# HW.net
KiCad netlist of a schematic drawn in Altium Designer
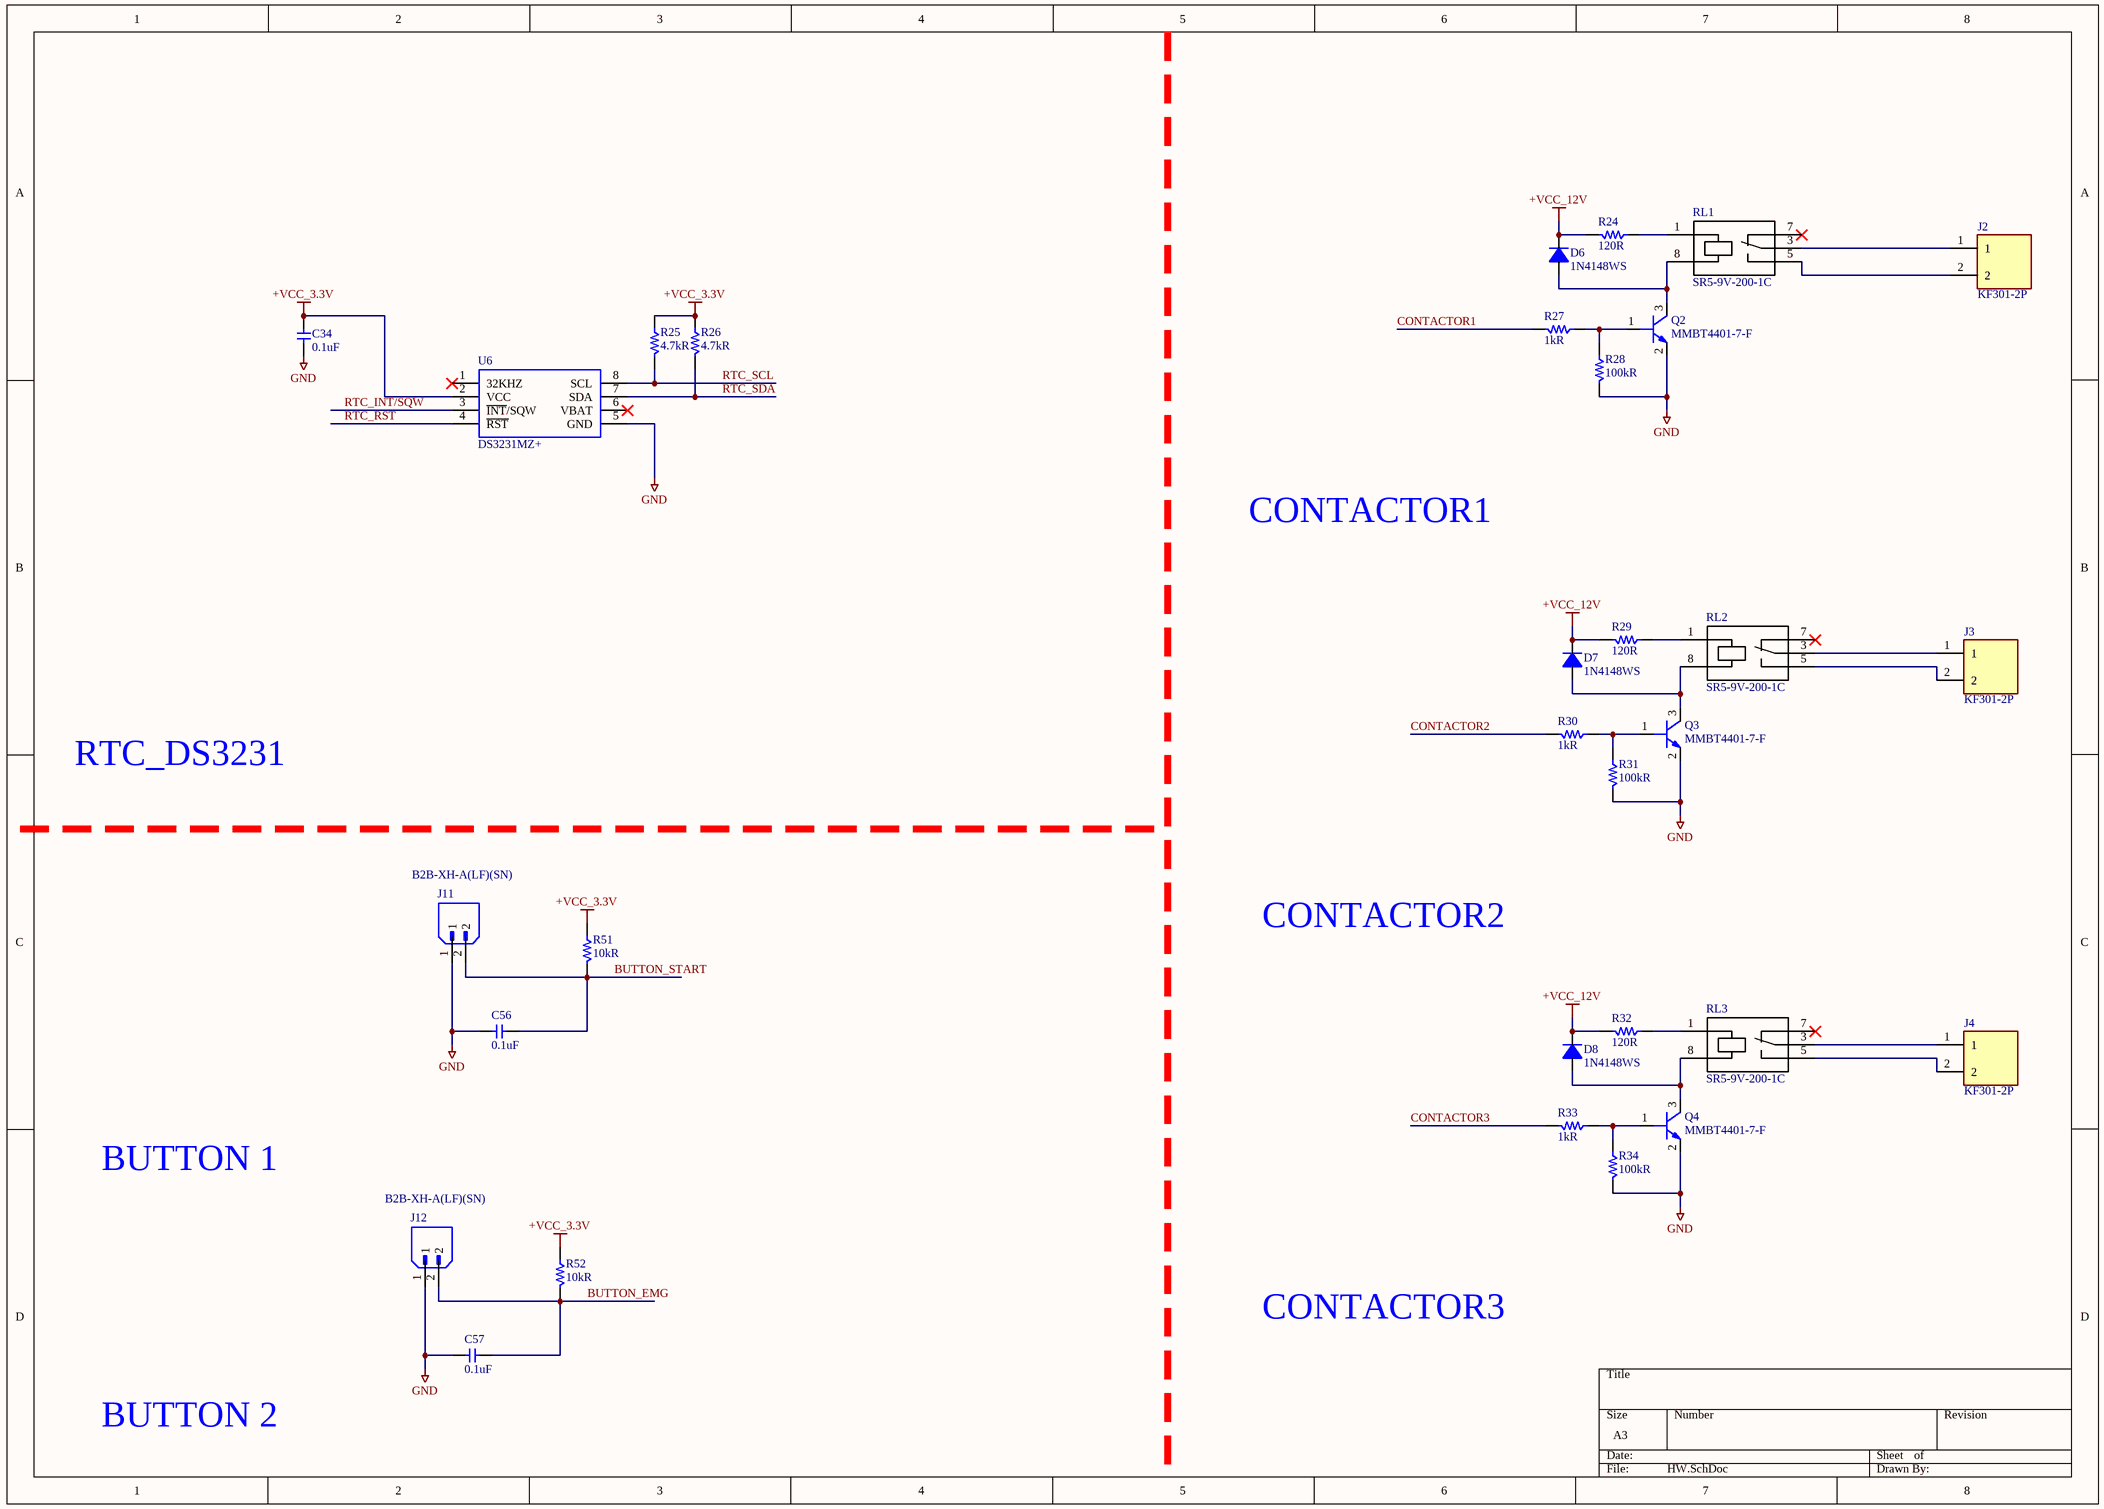
[diagram p0: HW.SchDoc]

(export (version "E")
  (design (tool "Eeschema 10.0.6"))
  (components
    (comp (ref "C34")
      (value "0.1uF")
      (footprint "CAP 0402 (1005)")
      (description "50V 100nF ±10% 0402 Multilayer Ceramic Capacitors MLCC - SMD/SMT ROHS")
      (fields
        (field (name "MANUFACTURER") "Samwha Capacitor")
        (field (name "MANUFACTURER PART NUMBER") "CS1005X7R104K500NR")
      )
      (libsource (lib "BSR NODE_V2.0 LIB") (part "CAP0402 0.1uF 50V"))
    )
    (comp (ref "C56")
      (value "0.1uF")
      (footprint "CAP 0402 (1005)")
      (description "50V 100nF ±10% 0402 Multilayer Ceramic Capacitors MLCC - SMD/SMT ROHS")
      (fields
        (field (name "MANUFACTURER") "Samwha Capacitor")
        (field (name "MANUFACTURER PART NUMBER") "CS1005X7R104K500NR")
      )
      (libsource (lib "BSR NODE_V2.0 LIB") (part "CAP0402 0.1uF 50V"))
    )
    (comp (ref "C57")
      (value "0.1uF")
      (footprint "CAP 0402 (1005)")
      (description "50V 100nF ±10% 0402 Multilayer Ceramic Capacitors MLCC - SMD/SMT ROHS")
      (fields
        (field (name "MANUFACTURER") "Samwha Capacitor")
        (field (name "MANUFACTURER PART NUMBER") "CS1005X7R104K500NR")
      )
      (libsource (lib "BSR NODE_V2.0 LIB") (part "CAP0402 0.1uF 50V"))
    )
    (comp (ref "D6")
      (value "1N4148WS")
      (footprint "SOD323")
      (description "DIODE GEN PURP 75V 150MA SOD323F")
      (fields (field (name "MANUFACTURER") "Fairchild/ON Semiconductor"))
      (libsource (lib "BSR") (part "DIO 1N4148WS"))
    )
    (comp (ref "D7")
      (value "1N4148WS")
      (footprint "SOD323")
      (description "DIODE GEN PURP 75V 150MA SOD323F")
      (fields (field (name "MANUFACTURER") "Fairchild/ON Semiconductor"))
      (libsource (lib "BSR") (part "DIO 1N4148WS"))
    )
    (comp (ref "D8")
      (value "1N4148WS")
      (footprint "SOD323")
      (description "DIODE GEN PURP 75V 150MA SOD323F")
      (fields (field (name "MANUFACTURER") "Fairchild/ON Semiconductor"))
      (libsource (lib "BSR") (part "DIO 1N4148WS"))
    )
    (comp (ref "J2")
      (value "KF301-2P")
      (footprint "HANDSON_KF301-2P")
      (description "2 Pin Terminal Block 5mm Pitch")
      (fields (field (name "MF") "Handson Technology"))
      (libsource (lib "KF301-2P") (part "KF301-2P"))
    )
    (comp (ref "J3")
      (value "KF301-2P")
      (footprint "HANDSON_KF301-2P")
      (description "2 Pin Terminal Block 5mm Pitch")
      (fields (field (name "MF") "Handson Technology"))
      (libsource (lib "KF301-2P") (part "KF301-2P"))
    )
    (comp (ref "J4")
      (value "KF301-2P")
      (footprint "HANDSON_KF301-2P")
      (description "2 Pin Terminal Block 5mm Pitch")
      (fields (field (name "MF") "Handson Technology"))
      (libsource (lib "KF301-2P") (part "KF301-2P"))
    )
    (comp (ref "J11")
      (value "B2B-XH-A(LF)(SN)")
      (footprint "JST_B2B-XH-A(LF)(SN)")
      (description "Connector Header Through Hole 2 position 0.098 (2.50mm)")
      (fields (field (name "MF") "JST Sales"))
      (libsource (lib "B2B-XH-A(LF)(SN)") (part "B2B-XH-A(LF)(SN)"))
    )
    (comp (ref "J12")
      (value "B2B-XH-A(LF)(SN)")
      (footprint "JST_B2B-XH-A(LF)(SN)")
      (description "Connector Header Through Hole 2 position 0.098 (2.50mm)")
      (fields (field (name "MF") "JST Sales"))
      (libsource (lib "B2B-XH-A(LF)(SN)") (part "B2B-XH-A(LF)(SN)"))
    )
    (comp (ref "Q2")
      (value "MMBT4401-7-F")
      (footprint "SOT-23-3")
      (description "TRANS NPN 40V 0.6A SMD SOT23-3")
      (fields (field (name "MANUFACTURER") "Diodes Incorporated"))
      (libsource (lib "BSR") (part "TRANS MMBT4401-7-F"))
    )
    (comp (ref "Q3")
      (value "MMBT4401-7-F")
      (footprint "SOT-23-3")
      (description "TRANS NPN 40V 0.6A SMD SOT23-3")
      (fields (field (name "MANUFACTURER") "Diodes Incorporated"))
      (libsource (lib "BSR") (part "TRANS MMBT4401-7-F"))
    )
    (comp (ref "Q4")
      (value "MMBT4401-7-F")
      (footprint "SOT-23-3")
      (description "TRANS NPN 40V 0.6A SMD SOT23-3")
      (fields (field (name "MANUFACTURER") "Diodes Incorporated"))
      (libsource (lib "BSR") (part "TRANS MMBT4401-7-F"))
    )
    (comp (ref "R24")
      (value "120R")
      (footprint "RES 0603 (1608)")
      (description "±1% 120Ω 0603 Chip Resistor - Surface Mount ROHS")
      (fields (field (name "MANUFACTURER") "VO") (field (name "MANUFACTURER PART NUMBER") "SCR0603F120R"))
      (libsource (lib "BSR NODE_V2.0 LIB") (part "RES0603 120R 1%"))
    )
    (comp (ref "R25")
      (value "4.7kR")
      (footprint "RES 0402 (1005)")
      (description "±1% 4.7kΩ 0402 Chip Resistor - Surface Mount ROHS")
      (fields (field (name "MANUFACTURER") "VO") (field (name "MANUFACTURER PART NUMBER") "SCR0402F4K7"))
      (libsource (lib "BSR NODE_V2.0 LIB") (part "RES0402 4.7kR 1%"))
    )
    (comp (ref "R26")
      (value "4.7kR")
      (footprint "RES 0402 (1005)")
      (description "±1% 4.7kΩ 0402 Chip Resistor - Surface Mount ROHS")
      (fields (field (name "MANUFACTURER") "VO") (field (name "MANUFACTURER PART NUMBER") "SCR0402F4K7"))
      (libsource (lib "BSR NODE_V2.0 LIB") (part "RES0402 4.7kR 1%"))
    )
    (comp (ref "R27")
      (value "1kR")
      (footprint "RES 0402 (1005)")
      (description "±5% 1kΩ 0402 Chip Resistor - Surface Mount ROHS")
      (fields (field (name "MANUFACTURER") "VO") (field (name "MANUFACTURER PART NUMBER") "SCR0402J1K"))
      (libsource (lib "BSR NODE_V2.0 LIB") (part "RES0402 1kR 1%"))
    )
    (comp (ref "R28")
      (value "100kR")
      (footprint "RES 0402 (1005)")
      (description "±1% 100kΩ 0402 Chip Resistor - Surface Mount ROHS")
      (fields (field (name "MANUFACTURER") "VO") (field (name "MANUFACTURER PART NUMBER") "SCR0402F100K"))
      (libsource (lib "BSR NODE_V2.0 LIB") (part "RES0402 100kR 1%"))
    )
    (comp (ref "R29")
      (value "120R")
      (footprint "RES 0603 (1608)")
      (description "±1% 120Ω 0603 Chip Resistor - Surface Mount ROHS")
      (fields (field (name "MANUFACTURER") "VO") (field (name "MANUFACTURER PART NUMBER") "SCR0603F120R"))
      (libsource (lib "BSR NODE_V2.0 LIB") (part "RES0603 120R 1%"))
    )
    (comp (ref "R30")
      (value "1kR")
      (footprint "RES 0402 (1005)")
      (description "±5% 1kΩ 0402 Chip Resistor - Surface Mount ROHS")
      (fields (field (name "MANUFACTURER") "VO") (field (name "MANUFACTURER PART NUMBER") "SCR0402J1K"))
      (libsource (lib "BSR NODE_V2.0 LIB") (part "RES0402 1kR 1%"))
    )
    (comp (ref "R31")
      (value "100kR")
      (footprint "RES 0402 (1005)")
      (description "±1% 100kΩ 0402 Chip Resistor - Surface Mount ROHS")
      (fields (field (name "MANUFACTURER") "VO") (field (name "MANUFACTURER PART NUMBER") "SCR0402F100K"))
      (libsource (lib "BSR NODE_V2.0 LIB") (part "RES0402 100kR 1%"))
    )
    (comp (ref "R32")
      (value "120R")
      (footprint "RES 0603 (1608)")
      (description "±1% 120Ω 0603 Chip Resistor - Surface Mount ROHS")
      (fields (field (name "MANUFACTURER") "VO") (field (name "MANUFACTURER PART NUMBER") "SCR0603F120R"))
      (libsource (lib "BSR NODE_V2.0 LIB") (part "RES0603 120R 1%"))
    )
    (comp (ref "R33")
      (value "1kR")
      (footprint "RES 0402 (1005)")
      (description "±5% 1kΩ 0402 Chip Resistor - Surface Mount ROHS")
      (fields (field (name "MANUFACTURER") "VO") (field (name "MANUFACTURER PART NUMBER") "SCR0402J1K"))
      (libsource (lib "BSR NODE_V2.0 LIB") (part "RES0402 1kR 1%"))
    )
    (comp (ref "R34")
      (value "100kR")
      (footprint "RES 0402 (1005)")
      (description "±1% 100kΩ 0402 Chip Resistor - Surface Mount ROHS")
      (fields (field (name "MANUFACTURER") "VO") (field (name "MANUFACTURER PART NUMBER") "SCR0402F100K"))
      (libsource (lib "BSR NODE_V2.0 LIB") (part "RES0402 100kR 1%"))
    )
    (comp (ref "R51")
      (value "10kR")
      (footprint "RES 0402 (1005)")
      (description "±1% 10kΩ 0402 Chip Resistor - Surface Mount ROHS")
      (fields (field (name "MANUFACTURER") "VO") (field (name "MANUFACTURER PART NUMBER") "SCR0402F10K"))
      (libsource (lib "BSR NODE_V2.0 LIB") (part "RES0402 10kR 1%"))
    )
    (comp (ref "R52")
      (value "10kR")
      (footprint "RES 0402 (1005)")
      (description "±1% 10kΩ 0402 Chip Resistor - Surface Mount ROHS")
      (fields (field (name "MANUFACTURER") "VO") (field (name "MANUFACTURER PART NUMBER") "SCR0402F10K"))
      (libsource (lib "BSR NODE_V2.0 LIB") (part "RES0402 10kR 1%"))
    )
    (comp (ref "RL1")
      (value "SR5-9V-200-1C")
      (footprint "RELAY SR5-9V-200-1C")
      (description "15.6 X 10.6 X 11.8 MM, 9 V, 1 A,")
      (fields (field (name "MANUFACTURER") "CUI Devices"))
      (libsource (lib "BSR") (part "RELAY 1 FORM C SR5-9V-200-1C"))
    )
    (comp (ref "RL2")
      (value "SR5-9V-200-1C")
      (footprint "RELAY SR5-9V-200-1C")
      (description "15.6 X 10.6 X 11.8 MM, 9 V, 1 A,")
      (fields (field (name "MANUFACTURER") "CUI Devices"))
      (libsource (lib "BSR") (part "RELAY 1 FORM C SR5-9V-200-1C"))
    )
    (comp (ref "RL3")
      (value "SR5-9V-200-1C")
      (footprint "RELAY SR5-9V-200-1C")
      (description "15.6 X 10.6 X 11.8 MM, 9 V, 1 A,")
      (fields (field (name "MANUFACTURER") "CUI Devices"))
      (libsource (lib "BSR") (part "RELAY 1 FORM C SR5-9V-200-1C"))
    )
    (comp (ref "U6")
      (value "DS3231MZ+")
      (footprint "SOIC127P600X175-8N")
      (description "I2C SOP-8 Real-time Clocks (RTC) ROHS")
      (fields
        (field (name "MANUFACTURER") "Analog Devices Inc./Maxim Integrated")
        (field (name "MANUFACTURER PART NUMBER") "DS3231MZ+TRL")
      )
      (libsource (lib "BSR NODE_V2.0 LIB") (part "IC DS3231MZ+"))
    )
  )
  (nets
    (net (code "1") (name "+VCC_3.3V") (class "Default")
      (node (ref "C34") (pin "1") (pinfunction "1_1") (pintype "passive"))
      (node (ref "R25") (pin "2") (pinfunction "2_2") (pintype "passive"))
      (node (ref "R26") (pin "2") (pinfunction "2_2") (pintype "passive"))
      (node (ref "R51") (pin "2") (pinfunction "2_2") (pintype "passive"))
      (node (ref "R52") (pin "2") (pinfunction "2_2") (pintype "passive"))
      (node (ref "U6") (pin "2") (pinfunction "VCC_2") (pintype "passive"))
    )
    (net (code "2") (name "+VCC_12V") (class "Default")
      (node (ref "D6") (pin "1") (pinfunction "K_1") (pintype "passive"))
      (node (ref "D7") (pin "1") (pinfunction "K_1") (pintype "passive"))
      (node (ref "D8") (pin "1") (pinfunction "K_1") (pintype "passive"))
      (node (ref "R24") (pin "1") (pinfunction "1_1") (pintype "passive"))
      (node (ref "R29") (pin "1") (pinfunction "1_1") (pintype "passive"))
      (node (ref "R32") (pin "1") (pinfunction "1_1") (pintype "passive"))
    )
    (net (code "3") (name "/BUTTON_EMG") (class "Default")
      (node (ref "C57") (pin "1") (pinfunction "1_1") (pintype "passive"))
      (node (ref "J12") (pin "2") (pinfunction "2_2") (pintype "passive"))
      (node (ref "R52") (pin "1") (pinfunction "1_1") (pintype "passive"))
    )
    (net (code "4") (name "/BUTTON_START") (class "Default")
      (node (ref "C56") (pin "1") (pinfunction "1_1") (pintype "passive"))
      (node (ref "J11") (pin "2") (pinfunction "2_2") (pintype "passive"))
      (node (ref "R51") (pin "1") (pinfunction "1_1") (pintype "passive"))
    )
    (net (code "5") (name "/CONTACTOR1") (class "Default")
      (node (ref "R27") (pin "1") (pinfunction "1_1") (pintype "passive"))
    )
    (net (code "6") (name "/CONTACTOR2") (class "Default")
      (node (ref "R30") (pin "1") (pinfunction "1_1") (pintype "passive"))
    )
    (net (code "7") (name "/CONTACTOR3") (class "Default")
      (node (ref "R33") (pin "1") (pinfunction "1_1") (pintype "passive"))
    )
    (net (code "8") (name "/RTC_INT{slash}SQW") (class "Default")
      (node (ref "U6") (pin "3") (pinfunction "~{INT}/SQW_3") (pintype "passive"))
    )
    (net (code "9") (name "/RTC_RST") (class "Default")
      (node (ref "U6") (pin "4") (pinfunction "~{RST}_4") (pintype "passive"))
    )
    (net (code "10") (name "/RTC_SCL") (class "Default")
      (node (ref "R25") (pin "1") (pinfunction "1_1") (pintype "passive"))
      (node (ref "U6") (pin "8") (pinfunction "SCL_8") (pintype "passive"))
    )
    (net (code "11") (name "/RTC_SDA") (class "Default")
      (node (ref "R26") (pin "1") (pinfunction "1_1") (pintype "passive"))
      (node (ref "U6") (pin "7") (pinfunction "SDA_7") (pintype "passive"))
    )
    (net (code "12") (name "GND") (class "Default")
      (node (ref "C34") (pin "2") (pinfunction "2_2") (pintype "passive"))
      (node (ref "C56") (pin "2") (pinfunction "2_2") (pintype "passive"))
      (node (ref "C57") (pin "2") (pinfunction "2_2") (pintype "passive"))
      (node (ref "J11") (pin "1") (pinfunction "1_1") (pintype "passive"))
      (node (ref "J12") (pin "1") (pinfunction "1_1") (pintype "passive"))
      (node (ref "Q2") (pin "2") (pinfunction "E_2") (pintype "passive"))
      (node (ref "Q3") (pin "2") (pinfunction "E_2") (pintype "passive"))
      (node (ref "Q4") (pin "2") (pinfunction "E_2") (pintype "passive"))
      (node (ref "R28") (pin "1") (pinfunction "1_1") (pintype "passive"))
      (node (ref "R31") (pin "1") (pinfunction "1_1") (pintype "passive"))
      (node (ref "R34") (pin "1") (pinfunction "1_1") (pintype "passive"))
      (node (ref "U6") (pin "5") (pinfunction "GND_5") (pintype "passive"))
    )
    (net (code "13") (name "Net-(D6-A)") (class "Default")
      (node (ref "D6") (pin "2") (pinfunction "A_2") (pintype "passive"))
      (node (ref "Q2") (pin "3") (pinfunction "C_3") (pintype "passive"))
      (node (ref "RL1") (pin "8") (pinfunction "C2_8") (pintype "passive"))
    )
    (net (code "14") (name "Net-(D7-A)") (class "Default")
      (node (ref "D7") (pin "2") (pinfunction "A_2") (pintype "passive"))
      (node (ref "Q3") (pin "3") (pinfunction "C_3") (pintype "passive"))
      (node (ref "RL2") (pin "8") (pinfunction "C2_8") (pintype "passive"))
    )
    (net (code "15") (name "Net-(D8-A)") (class "Default")
      (node (ref "D8") (pin "2") (pinfunction "A_2") (pintype "passive"))
      (node (ref "Q4") (pin "3") (pinfunction "C_3") (pintype "passive"))
      (node (ref "RL3") (pin "8") (pinfunction "C2_8") (pintype "passive"))
    )
    (net (code "16") (name "Net-(Q2-B)") (class "Default")
      (node (ref "Q2") (pin "1") (pinfunction "B_1") (pintype "passive"))
      (node (ref "R27") (pin "2") (pinfunction "2_2") (pintype "passive"))
      (node (ref "R28") (pin "2") (pinfunction "2_2") (pintype "passive"))
    )
    (net (code "17") (name "Net-(Q3-B)") (class "Default")
      (node (ref "Q3") (pin "1") (pinfunction "B_1") (pintype "passive"))
      (node (ref "R30") (pin "2") (pinfunction "2_2") (pintype "passive"))
      (node (ref "R31") (pin "2") (pinfunction "2_2") (pintype "passive"))
    )
    (net (code "18") (name "Net-(Q4-B)") (class "Default")
      (node (ref "Q4") (pin "1") (pinfunction "B_1") (pintype "passive"))
      (node (ref "R33") (pin "2") (pinfunction "2_2") (pintype "passive"))
      (node (ref "R34") (pin "2") (pinfunction "2_2") (pintype "passive"))
    )
    (net (code "19") (name "Net-(RL1-C)") (class "Default")
      (node (ref "J2") (pin "1") (pinfunction "1_1") (pintype "passive"))
      (node (ref "RL1") (pin "3") (pinfunction "C_3") (pintype "passive"))
    )
    (net (code "20") (name "Net-(RL1-C1)") (class "Default")
      (node (ref "R24") (pin "2") (pinfunction "2_2") (pintype "passive"))
      (node (ref "RL1") (pin "1") (pinfunction "C1_1") (pintype "passive"))
    )
    (net (code "21") (name "Net-(RL1-NO)") (class "Default")
      (node (ref "J2") (pin "2") (pinfunction "2_2") (pintype "passive"))
      (node (ref "RL1") (pin "5") (pinfunction "NO_5") (pintype "passive"))
    )
    (net (code "22") (name "Net-(RL2-C)") (class "Default")
      (node (ref "J3") (pin "1") (pinfunction "1_1") (pintype "passive"))
      (node (ref "RL2") (pin "3") (pinfunction "C_3") (pintype "passive"))
    )
    (net (code "23") (name "Net-(RL2-C1)") (class "Default")
      (node (ref "R29") (pin "2") (pinfunction "2_2") (pintype "passive"))
      (node (ref "RL2") (pin "1") (pinfunction "C1_1") (pintype "passive"))
    )
    (net (code "24") (name "Net-(RL2-NO)") (class "Default")
      (node (ref "J3") (pin "2") (pinfunction "2_2") (pintype "passive"))
      (node (ref "RL2") (pin "5") (pinfunction "NO_5") (pintype "passive"))
    )
    (net (code "25") (name "Net-(RL3-C)") (class "Default")
      (node (ref "J4") (pin "1") (pinfunction "1_1") (pintype "passive"))
      (node (ref "RL3") (pin "3") (pinfunction "C_3") (pintype "passive"))
    )
    (net (code "26") (name "Net-(RL3-C1)") (class "Default")
      (node (ref "R32") (pin "2") (pinfunction "2_2") (pintype "passive"))
      (node (ref "RL3") (pin "1") (pinfunction "C1_1") (pintype "passive"))
    )
    (net (code "27") (name "Net-(RL3-NO)") (class "Default")
      (node (ref "J4") (pin "2") (pinfunction "2_2") (pintype "passive"))
      (node (ref "RL3") (pin "5") (pinfunction "NO_5") (pintype "passive"))
    )
    (net (code "28") (name "unconnected-(RL1-NC-Pad7)") (class "Default")
      (node (ref "RL1") (pin "7") (pinfunction "NC_7") (pintype "passive+no_connect"))
    )
    (net (code "29") (name "unconnected-(RL2-NC-Pad7)") (class "Default")
      (node (ref "RL2") (pin "7") (pinfunction "NC_7") (pintype "passive+no_connect"))
    )
    (net (code "30") (name "unconnected-(RL3-NC-Pad7)") (class "Default")
      (node (ref "RL3") (pin "7") (pinfunction "NC_7") (pintype "passive+no_connect"))
    )
    (net (code "31") (name "unconnected-(U6-32KHZ-Pad1)") (class "Default")
      (node (ref "U6") (pin "1") (pinfunction "32KHZ_1") (pintype "passive+no_connect"))
    )
    (net (code "32") (name "unconnected-(U6-VBAT-Pad6)") (class "Default")
      (node (ref "U6") (pin "6") (pinfunction "VBAT_6") (pintype "passive+no_connect"))
    )
  )
)
